# SheetBYB2A.net
KiCad netlist of a schematic drawn in Altium Designer
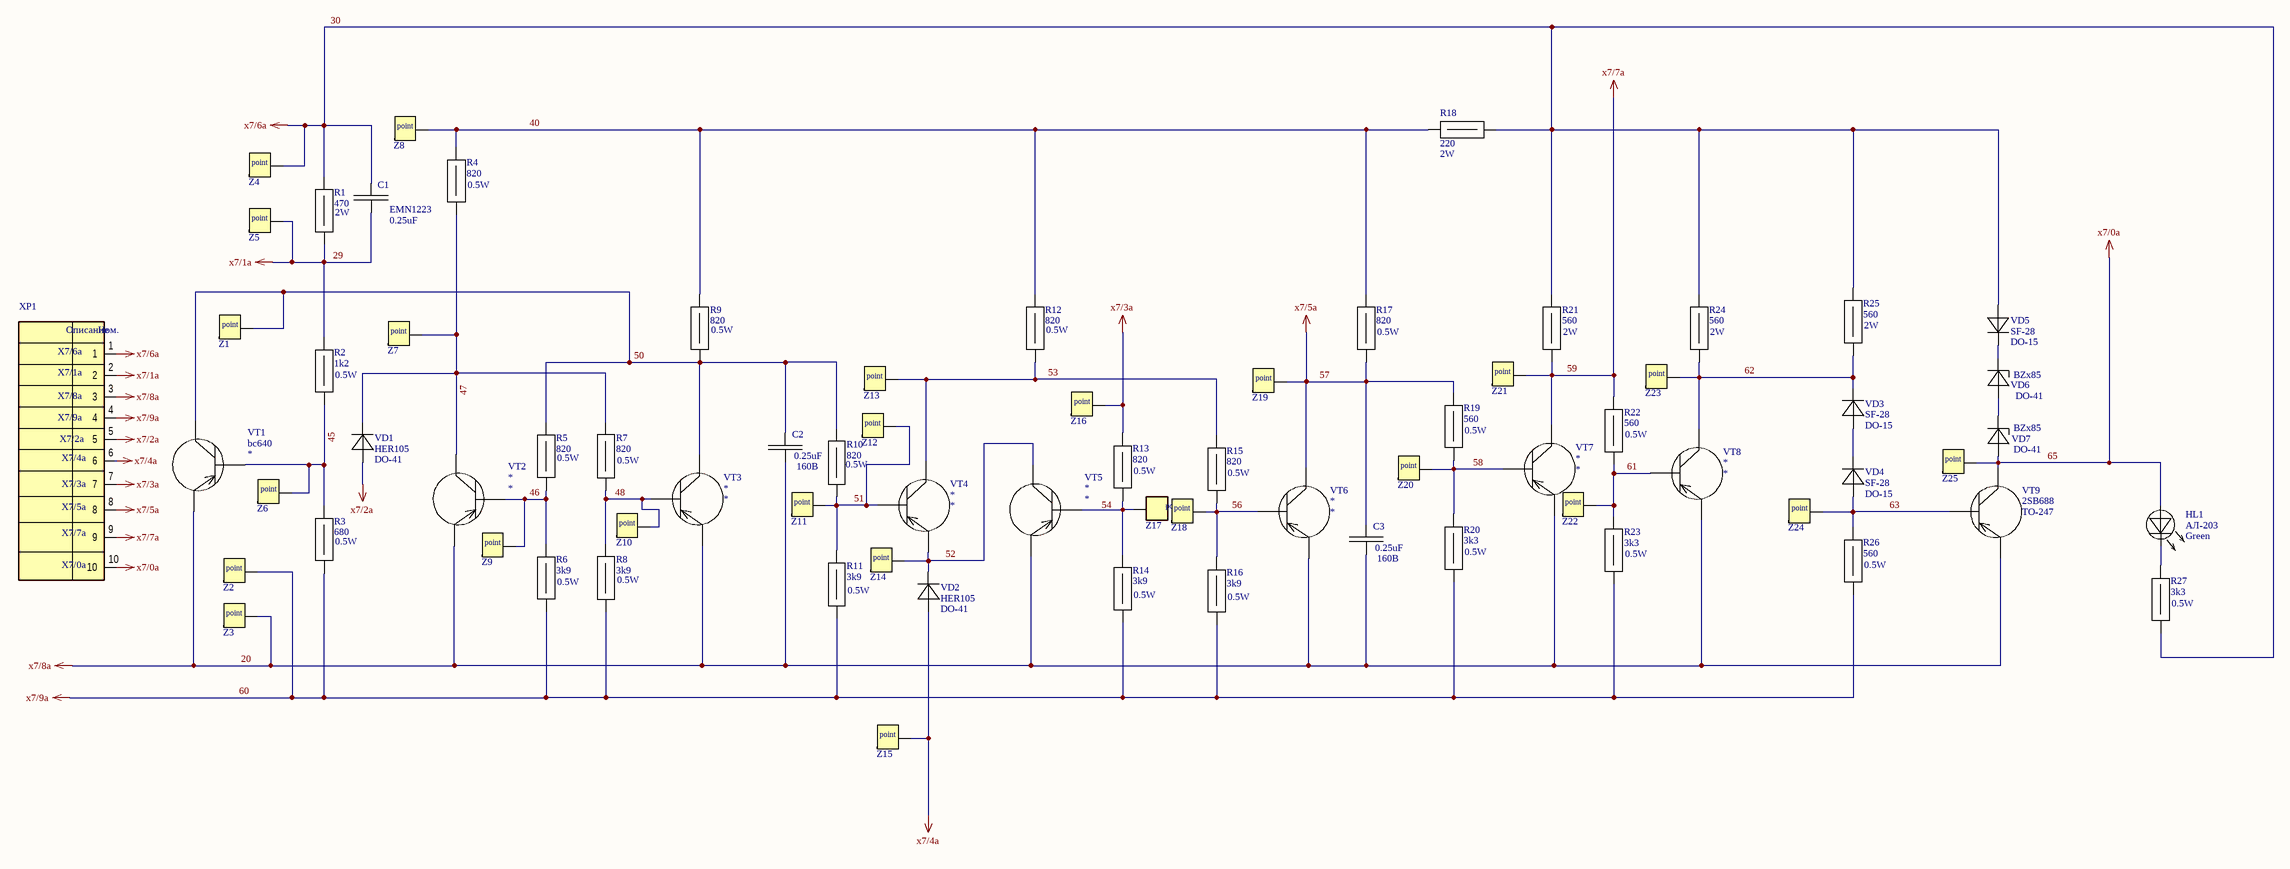
[diagram p0: SheetBYB2A.SchDoc]

(export (version "E")
  (design (tool "Eeschema 10.0.6"))
  (components
    (comp (ref "C1")
      (value "0.25uF")
      (footprint "Capasitor")
      (fields (field (name "MARKA") "EMN1223") (field (name "Comment") "Capasitor"))
      (libsource (lib "SchlibBYB2A") (part "Capasitor"))
    )
    (comp (ref "C2")
      (value "0.25uF")
      (footprint "Capasitor")
      (fields (field (name "VOLTAGE") "160B") (field (name "Comment") "Capasitor"))
      (libsource (lib "SchlibBYB2A") (part "Capasitor"))
    )
    (comp (ref "C3")
      (value "0.25uF")
      (footprint "Capasitor")
      (fields (field (name "VOLTAGE") "160B") (field (name "Comment") "Capasitor"))
      (libsource (lib "SchlibBYB2A") (part "Capasitor"))
    )
    (comp (ref "HL1")
      (value "Led")
      (footprint "GNLR")
      (fields (field (name "MARKA") "АЛ-203") (field (name "COLOR") "Green"))
      (libsource (lib "SchlibBYB2A") (part "Led"))
    )
    (comp (ref "R1")
      (value "470")
      (footprint "Resistor_2W")
      (fields (field (name "POWER") "2W") (field (name "Comment") "Resistor_1/2W"))
      (libsource (lib "SchlibBYB2A") (part "Resistor_1/2W"))
    )
    (comp (ref "R2")
      (value "1k2")
      (footprint "RESC5025L")
      (fields (field (name "POWER") "0.5W") (field (name "Comment") "Resistor_1/2W"))
      (libsource (lib "SchlibBYB2A") (part "Resistor_1/2W"))
    )
    (comp (ref "R3")
      (value "680")
      (footprint "RESC5025L")
      (fields (field (name "POWER") "0.5W") (field (name "Comment") "Resistor_1/2W"))
      (libsource (lib "SchlibBYB2A") (part "Resistor_1/2W"))
    )
    (comp (ref "R4")
      (value "820")
      (footprint "RESC5025L")
      (fields (field (name "POWER") "0.5W") (field (name "Comment") "Resistor_1/2W"))
      (libsource (lib "SchlibBYB2A") (part "Resistor_1/2W"))
    )
    (comp (ref "R5")
      (value "820")
      (footprint "RESC5025L")
      (fields (field (name "POWER") "0.5W") (field (name "Comment") "Resistor_1/2W"))
      (libsource (lib "SchlibBYB2A") (part "Resistor_1/2W"))
    )
    (comp (ref "R6")
      (value "3k9")
      (footprint "RESC5025L")
      (fields (field (name "POWER") "0.5W") (field (name "Comment") "Resistor_1/2W"))
      (libsource (lib "SchlibBYB2A") (part "Resistor_1/2W"))
    )
    (comp (ref "R7")
      (value "820")
      (footprint "RESC5025L")
      (fields (field (name "POWER") "0.5W") (field (name "Comment") "Resistor_1/2W"))
      (libsource (lib "SchlibBYB2A") (part "Resistor_1/2W"))
    )
    (comp (ref "R8")
      (value "3k9")
      (footprint "RESC5025L")
      (fields (field (name "POWER") "0.5W") (field (name "Comment") "Resistor_1/2W"))
      (libsource (lib "SchlibBYB2A") (part "Resistor_1/2W"))
    )
    (comp (ref "R9")
      (value "820")
      (footprint "RESC5025L")
      (fields (field (name "POWER") "0.5W") (field (name "Comment") "Resistor_1/2W"))
      (libsource (lib "SchlibBYB2A") (part "Resistor_1/2W"))
    )
    (comp (ref "R10")
      (value "820")
      (footprint "RESC5025L")
      (fields (field (name "POWER") "0.5W") (field (name "Comment") "Resistor_1/2W"))
      (libsource (lib "SchlibBYB2A") (part "Resistor_1/2W"))
    )
    (comp (ref "R11")
      (value "3k9")
      (footprint "RESC5025L")
      (fields (field (name "POWER") "0.5W") (field (name "Comment") "Resistor_1/2W"))
      (libsource (lib "SchlibBYB2A") (part "Resistor_1/2W"))
    )
    (comp (ref "R12")
      (value "820")
      (footprint "RESC5025L")
      (fields (field (name "POWER") "0.5W") (field (name "Comment") "Resistor_1/2W"))
      (libsource (lib "SchlibBYB2A") (part "Resistor_1/2W"))
    )
    (comp (ref "R13")
      (value "820")
      (footprint "RESC5025L")
      (fields (field (name "POWER") "0.5W") (field (name "Comment") "Resistor_1/2W"))
      (libsource (lib "SchlibBYB2A") (part "Resistor_1/2W"))
    )
    (comp (ref "R14")
      (value "3k9")
      (footprint "RESC5025L")
      (fields (field (name "POWER") "0.5W") (field (name "Comment") "Resistor_1/2W"))
      (libsource (lib "SchlibBYB2A") (part "Resistor_1/2W"))
    )
    (comp (ref "R15")
      (value "820")
      (footprint "RESC5025L")
      (fields (field (name "POWER") "0.5W") (field (name "Comment") "Resistor_1/2W"))
      (libsource (lib "SchlibBYB2A") (part "Resistor_1/2W"))
    )
    (comp (ref "R16")
      (value "3k9")
      (footprint "RESC5025L")
      (fields (field (name "POWER") "0.5W") (field (name "Comment") "Resistor_1/2W"))
      (libsource (lib "SchlibBYB2A") (part "Resistor_1/2W"))
    )
    (comp (ref "R17")
      (value "820")
      (footprint "RESC5025L")
      (fields (field (name "POWER") "0.5W") (field (name "Comment") "Resistor_1/2W"))
      (libsource (lib "SchlibBYB2A") (part "Resistor_1/2W"))
    )
    (comp (ref "R18")
      (value "220")
      (footprint "Resistor_2W")
      (fields (field (name "POWER") "2W") (field (name "Comment") "Resistor_1/2W"))
      (libsource (lib "SchlibBYB2A") (part "Resistor_1/2W"))
    )
    (comp (ref "R19")
      (value "560")
      (footprint "RESC5025L")
      (fields (field (name "POWER") "0.5W") (field (name "Comment") "Resistor_1/2W"))
      (libsource (lib "SchlibBYB2A") (part "Resistor_1/2W"))
    )
    (comp (ref "R20")
      (value "3k3")
      (footprint "RESC5025L")
      (fields (field (name "POWER") "0.5W") (field (name "Comment") "Resistor_1/2W"))
      (libsource (lib "SchlibBYB2A") (part "Resistor_1/2W"))
    )
    (comp (ref "R21")
      (value "560")
      (footprint "Resistor_2W")
      (fields (field (name "POWER") "2W") (field (name "Comment") "Resistor_1/2W"))
      (libsource (lib "SchlibBYB2A") (part "Resistor_1/2W"))
    )
    (comp (ref "R22")
      (value "560")
      (footprint "RESC5025L")
      (fields (field (name "POWER") "0.5W") (field (name "Comment") "Resistor_1/2W"))
      (libsource (lib "SchlibBYB2A") (part "Resistor_1/2W"))
    )
    (comp (ref "R23")
      (value "3k3")
      (footprint "RESC5025L")
      (fields (field (name "POWER") "0.5W") (field (name "Comment") "Resistor_1/2W"))
      (libsource (lib "SchlibBYB2A") (part "Resistor_1/2W"))
    )
    (comp (ref "R24")
      (value "560")
      (footprint "Resistor_2W")
      (fields (field (name "POWER") "2W") (field (name "Comment") "Resistor_1/2W"))
      (libsource (lib "SchlibBYB2A") (part "Resistor_1/2W"))
    )
    (comp (ref "R25")
      (value "560")
      (footprint "Resistor_2W")
      (fields (field (name "POWER") "2W") (field (name "Comment") "Resistor_1/2W"))
      (libsource (lib "SchlibBYB2A") (part "Resistor_1/2W"))
    )
    (comp (ref "R26")
      (value "560")
      (footprint "RESC5025L")
      (fields (field (name "POWER") "0.5W") (field (name "Comment") "Resistor_1/2W"))
      (libsource (lib "SchlibBYB2A") (part "Resistor_1/2W"))
    )
    (comp (ref "R27")
      (value "3k3")
      (footprint "RESC5025L")
      (fields (field (name "POWER") "0.5W") (field (name "Comment") "Resistor_1/2W"))
      (libsource (lib "SchlibBYB2A") (part "Resistor_1/2W"))
    )
    (comp (ref "VD1")
      (value "Diode")
      (footprint "DO-41-vertical")
      (fields (field (name "MARKA") "HER105") (field (name "PACKAGE") "DO-41"))
      (libsource (lib "SchlibBYB2A") (part "Diode"))
    )
    (comp (ref "VD2")
      (value "Diode")
      (footprint "DO-41-vertical")
      (fields (field (name "MARKA") "HER105") (field (name "PACKAGE") "DO-41"))
      (libsource (lib "SchlibBYB2A") (part "Diode"))
    )
    (comp (ref "VD3")
      (value "Diode")
      (footprint "DO-15-Vertical")
      (fields (field (name "MARKA") "SF-28") (field (name "PACKAGE") "DO-15"))
      (libsource (lib "SchlibBYB2A") (part "Diode"))
    )
    (comp (ref "VD4")
      (value "Diode")
      (footprint "DO-15-Vertical")
      (fields (field (name "MARKA") "SF-28") (field (name "PACKAGE") "DO-15"))
      (libsource (lib "SchlibBYB2A") (part "Diode"))
    )
    (comp (ref "VD5")
      (value "Diode")
      (footprint "DO-15-Vertical")
      (fields (field (name "MARKA") "SF-28") (field (name "PACKAGE") "DO-15"))
      (libsource (lib "SchlibBYB2A") (part "Diode"))
    )
    (comp (ref "VD6")
      (value "stabilizater")
      (footprint "DO-41-vertical")
      (fields (field (name "MARKA") "BZx85") (field (name "PACKAGE") "DO-41"))
      (libsource (lib "SchlibBYB2A") (part "stabilizater"))
    )
    (comp (ref "VD7")
      (value "stabilizater")
      (footprint "DO-41-vertical")
      (fields (field (name "MARKA") "BZx85") (field (name "PACKAGE") "DO-41"))
      (libsource (lib "SchlibBYB2A") (part "stabilizater"))
    )
    (comp (ref "VT1")
      (value "Bipolar Transistor")
      (footprint "TO-92")
      (fields (field (name "MARKA") "bc640") (field (name "PACKAGE") "*"))
      (libsource (lib "") (part "Bipolar Transistor_1"))
    )
    (comp (ref "VT2")
      (value "Bipolar Transistor")
      (footprint "TO-92")
      (fields (field (name "MARKA") "*") (field (name "PACKAGE") "*"))
      (libsource (lib "") (part "Bipolar Transistor_1"))
    )
    (comp (ref "VT3")
      (value "Bipolar Transistor")
      (footprint "TO-92")
      (fields (field (name "MARKA") "*") (field (name "PACKAGE") "*"))
      (libsource (lib "SchlibBYB2A") (part "Bipolar Transistor"))
    )
    (comp (ref "VT4")
      (value "Bipolar Transistor")
      (footprint "TO-92")
      (fields (field (name "MARKA") "*") (field (name "PACKAGE") "*"))
      (libsource (lib "SchlibBYB2A") (part "Bipolar Transistor"))
    )
    (comp (ref "VT5")
      (value "Bipolar Transistor")
      (footprint "TO-92")
      (fields (field (name "MARKA") "*") (field (name "PACKAGE") "*"))
      (libsource (lib "") (part "Bipolar Transistor_1"))
    )
    (comp (ref "VT6")
      (value "Bipolar Transistor")
      (footprint "TO-92")
      (fields (field (name "MARKA") "*") (field (name "PACKAGE") "*"))
      (libsource (lib "SchlibBYB2A") (part "Bipolar Transistor"))
    )
    (comp (ref "VT7")
      (value "Bipolar Transistor")
      (footprint "TO-92")
      (fields (field (name "MARKA") "*") (field (name "PACKAGE") "*"))
      (libsource (lib "SchlibBYB2A") (part "Bipolar Transistor"))
    )
    (comp (ref "VT8")
      (value "Bipolar Transistor")
      (footprint "TO-92")
      (fields (field (name "MARKA") "*") (field (name "PACKAGE") "*"))
      (libsource (lib "SchlibBYB2A") (part "Bipolar Transistor"))
    )
    (comp (ref "VT9")
      (value "2sb688")
      (footprint "TO-247-3")
      (fields (field (name "MARKA") "2SB688") (field (name "PACKAGE") "TO-247"))
      (libsource (lib "SchlibBYB2A") (part "2sb688"))
    )
    (comp (ref "XP1")
      (value "Connector")
      (footprint "Connector")
      (libsource (lib "SchlibBYB2A") (part "Connector"))
    )
    (comp (ref "Z1")
      (value "point_control")
      (footprint "point_control")
      (libsource (lib "SchlibBYB2A") (part "point_control"))
    )
    (comp (ref "Z2")
      (value "point_control")
      (footprint "point_control")
      (libsource (lib "SchlibBYB2A") (part "point_control"))
    )
    (comp (ref "Z3")
      (value "point_control")
      (footprint "point_control")
      (libsource (lib "SchlibBYB2A") (part "point_control"))
    )
    (comp (ref "Z4")
      (value "point_control")
      (footprint "point_control")
      (libsource (lib "SchlibBYB2A") (part "point_control"))
    )
    (comp (ref "Z5")
      (value "point_control")
      (footprint "point_control")
      (libsource (lib "SchlibBYB2A") (part "point_control"))
    )
    (comp (ref "Z6")
      (value "point_control")
      (footprint "point_control")
      (libsource (lib "SchlibBYB2A") (part "point_control"))
    )
    (comp (ref "Z7")
      (value "point_control")
      (footprint "point_control")
      (libsource (lib "SchlibBYB2A") (part "point_control"))
    )
    (comp (ref "Z8")
      (value "point_control")
      (footprint "point_control")
      (libsource (lib "SchlibBYB2A") (part "point_control"))
    )
    (comp (ref "Z9")
      (value "point_control")
      (footprint "point_control")
      (libsource (lib "SchlibBYB2A") (part "point_control"))
    )
    (comp (ref "Z10")
      (value "point_control")
      (footprint "point_control")
      (libsource (lib "SchlibBYB2A") (part "point_control"))
    )
    (comp (ref "Z11")
      (value "point_control")
      (footprint "point_control")
      (libsource (lib "SchlibBYB2A") (part "point_control"))
    )
    (comp (ref "Z12")
      (value "point_control")
      (footprint "point_control")
      (libsource (lib "SchlibBYB2A") (part "point_control"))
    )
    (comp (ref "Z13")
      (value "point_control")
      (footprint "point_control")
      (libsource (lib "SchlibBYB2A") (part "point_control"))
    )
    (comp (ref "Z14")
      (value "point_control")
      (footprint "point_control")
      (libsource (lib "SchlibBYB2A") (part "point_control"))
    )
    (comp (ref "Z15")
      (value "point_control")
      (footprint "point_control")
      (libsource (lib "SchlibBYB2A") (part "point_control"))
    )
    (comp (ref "Z16")
      (value "point_control")
      (footprint "point_control")
      (libsource (lib "SchlibBYB2A") (part "point_control"))
    )
    (comp (ref "Z17")
      (value "point_control")
      (footprint "point_control")
      (libsource (lib "") (part "point_control_1"))
    )
    (comp (ref "Z18")
      (value "point_control")
      (footprint "point_control")
      (libsource (lib "SchlibBYB2A") (part "point_control"))
    )
    (comp (ref "Z19")
      (value "point_control")
      (footprint "point_control")
      (libsource (lib "SchlibBYB2A") (part "point_control"))
    )
    (comp (ref "Z20")
      (value "point_control")
      (footprint "point_control")
      (libsource (lib "SchlibBYB2A") (part "point_control"))
    )
    (comp (ref "Z21")
      (value "point_control")
      (footprint "point_control")
      (libsource (lib "SchlibBYB2A") (part "point_control"))
    )
    (comp (ref "Z22")
      (value "point_control")
      (footprint "point_control")
      (libsource (lib "SchlibBYB2A") (part "point_control"))
    )
    (comp (ref "Z23")
      (value "point_control")
      (footprint "point_control")
      (libsource (lib "SchlibBYB2A") (part "point_control"))
    )
    (comp (ref "Z24")
      (value "point_control")
      (footprint "point_control")
      (libsource (lib "SchlibBYB2A") (part "point_control"))
    )
    (comp (ref "Z25")
      (value "point_control")
      (footprint "point_control")
      (libsource (lib "SchlibBYB2A") (part "point_control"))
    )
  )
  (nets
    (net (code "2") (name "/40") (class "Default")
      (node (ref "R12") (pin "2") (pinfunction "2_2") (pintype "passive"))
      (node (ref "R17") (pin "2") (pinfunction "2_2") (pintype "passive"))
      (node (ref "R18") (pin "2") (pinfunction "2_2") (pintype "passive"))
      (node (ref "R4") (pin "2") (pinfunction "2_2") (pintype "passive"))
      (node (ref "R9") (pin "2") (pinfunction "2_2") (pintype "passive"))
      (node (ref "Z8") (pin "1") (pinfunction "1_1") (pintype "passive"))
    )
    (net (code "3") (name "/45") (class "Default")
      (node (ref "R2") (pin "1") (pinfunction "1_1") (pintype "passive"))
      (node (ref "R3") (pin "2") (pinfunction "2_2") (pintype "passive"))
      (node (ref "VT1") (pin "3") (pinfunction "3_3") (pintype "passive"))
      (node (ref "Z6") (pin "1") (pinfunction "1_1") (pintype "passive"))
    )
    (net (code "4") (name "/46") (class "Default")
      (node (ref "R5") (pin "1") (pinfunction "1_1") (pintype "passive"))
      (node (ref "R6") (pin "2") (pinfunction "2_2") (pintype "passive"))
      (node (ref "VT2") (pin "3") (pinfunction "3_3") (pintype "passive"))
      (node (ref "Z9") (pin "1") (pinfunction "1_1") (pintype "passive"))
    )
    (net (code "5") (name "/47") (class "Default")
      (node (ref "R4") (pin "1") (pinfunction "1_1") (pintype "passive"))
      (node (ref "R7") (pin "2") (pinfunction "2_2") (pintype "passive"))
      (node (ref "VD1") (pin "2") (pinfunction "2_2") (pintype "passive"))
      (node (ref "VT2") (pin "2") (pinfunction "2_2") (pintype "passive"))
      (node (ref "Z7") (pin "1") (pinfunction "1_1") (pintype "passive"))
    )
    (net (code "6") (name "/48") (class "Default")
      (node (ref "R7") (pin "1") (pinfunction "1_1") (pintype "passive"))
      (node (ref "R8") (pin "2") (pinfunction "2_2") (pintype "passive"))
      (node (ref "VT3") (pin "3") (pinfunction "3_3") (pintype "passive"))
      (node (ref "Z10") (pin "1") (pinfunction "1_1") (pintype "passive"))
    )
    (net (code "7") (name "/50") (class "Default")
      (node (ref "C2") (pin "1") (pinfunction "1_1") (pintype "passive"))
      (node (ref "R10") (pin "2") (pinfunction "2_2") (pintype "passive"))
      (node (ref "R5") (pin "2") (pinfunction "2_2") (pintype "passive"))
      (node (ref "R9") (pin "1") (pinfunction "1_1") (pintype "passive"))
      (node (ref "VT1") (pin "2") (pinfunction "2_2") (pintype "passive"))
      (node (ref "VT3") (pin "2") (pinfunction "2_2") (pintype "passive"))
      (node (ref "Z1") (pin "1") (pinfunction "1_1") (pintype "passive"))
    )
    (net (code "8") (name "/51") (class "Default")
      (node (ref "R10") (pin "1") (pinfunction "1_1") (pintype "passive"))
      (node (ref "R11") (pin "2") (pinfunction "2_2") (pintype "passive"))
      (node (ref "VT4") (pin "3") (pinfunction "3_3") (pintype "passive"))
      (node (ref "Z11") (pin "1") (pinfunction "1_1") (pintype "passive"))
      (node (ref "Z12") (pin "1") (pinfunction "1_1") (pintype "passive"))
    )
    (net (code "9") (name "/52") (class "Default")
      (node (ref "VD2") (pin "2") (pinfunction "2_2") (pintype "passive"))
      (node (ref "VT4") (pin "1") (pinfunction "1_1") (pintype "passive"))
      (node (ref "VT5") (pin "2") (pinfunction "2_2") (pintype "passive"))
      (node (ref "Z14") (pin "1") (pinfunction "1_1") (pintype "passive"))
    )
    (net (code "10") (name "/53") (class "Default")
      (node (ref "R12") (pin "1") (pinfunction "1_1") (pintype "passive"))
      (node (ref "R15") (pin "2") (pinfunction "2_2") (pintype "passive"))
      (node (ref "VT4") (pin "2") (pinfunction "2_2") (pintype "passive"))
      (node (ref "Z13") (pin "1") (pinfunction "1_1") (pintype "passive"))
    )
    (net (code "12") (name "/56") (class "Default")
      (node (ref "R15") (pin "1") (pinfunction "1_1") (pintype "passive"))
      (node (ref "R16") (pin "2") (pinfunction "2_2") (pintype "passive"))
      (node (ref "VT6") (pin "3") (pinfunction "3_3") (pintype "passive"))
      (node (ref "Z18") (pin "1") (pinfunction "1_1") (pintype "passive"))
    )
    (net (code "13") (name "/58") (class "Default")
      (node (ref "R19") (pin "1") (pinfunction "1_1") (pintype "passive"))
      (node (ref "R20") (pin "2") (pinfunction "2_2") (pintype "passive"))
      (node (ref "VT7") (pin "3") (pinfunction "3_3") (pintype "passive"))
      (node (ref "Z20") (pin "1") (pinfunction "1_1") (pintype "passive"))
    )
    (net (code "14") (name "/61") (class "Default")
      (node (ref "R22") (pin "1") (pinfunction "1_1") (pintype "passive"))
      (node (ref "R23") (pin "2") (pinfunction "2_2") (pintype "passive"))
      (node (ref "VT8") (pin "3") (pinfunction "3_3") (pintype "passive"))
      (node (ref "Z22") (pin "1") (pinfunction "1_1") (pintype "passive"))
    )
    (net (code "15") (name "/62") (class "Default")
      (node (ref "R24") (pin "1") (pinfunction "1_1") (pintype "passive"))
      (node (ref "R25") (pin "1") (pinfunction "1_1") (pintype "passive"))
      (node (ref "VD3") (pin "2") (pinfunction "2_2") (pintype "passive"))
      (node (ref "VT8") (pin "2") (pinfunction "2_2") (pintype "passive"))
      (node (ref "Z23") (pin "1") (pinfunction "1_1") (pintype "passive"))
    )
    (net (code "16") (name "/63") (class "Default")
      (node (ref "R26") (pin "2") (pinfunction "2_2") (pintype "passive"))
      (node (ref "VD4") (pin "1") (pinfunction "1_1") (pintype "passive"))
      (node (ref "VT9") (pin "1") (pinfunction "1_1") (pintype "passive"))
      (node (ref "Z24") (pin "1") (pinfunction "1_1") (pintype "passive"))
    )
    (net (code "17") (name "Net-(HL1-Pad2)") (class "Default")
      (node (ref "HL1") (pin "2") (pinfunction "2_2") (pintype "passive"))
      (node (ref "R27") (pin "2") (pinfunction "2_2") (pintype "passive"))
    )
    (net (code "18") (name "Net-(R13-Pad1)") (class "Default")
      (node (ref "R13") (pin "1") (pinfunction "1_1") (pintype "passive"))
      (node (ref "R14") (pin "2") (pinfunction "2_2") (pintype "passive"))
      (node (ref "VT5") (pin "3") (pinfunction "3_3") (pintype "passive"))
      (node (ref "Z17") (pin "1") (pinfunction "1_1") (pintype "passive"))
    )
    (net (code "19") (name "Net-(VD3-Pad1)") (class "Default")
      (node (ref "VD3") (pin "1") (pinfunction "1_1") (pintype "passive"))
      (node (ref "VD4") (pin "2") (pinfunction "2_2") (pintype "passive"))
    )
    (net (code "20") (name "Net-(VD5-Pad2)") (class "Default")
      (node (ref "VD5") (pin "2") (pinfunction "2_2") (pintype "passive"))
      (node (ref "VD6") (pin "2") (pinfunction "2_2") (pintype "passive"))
    )
    (net (code "21") (name "Net-(VD6-Pad1)") (class "Default")
      (node (ref "VD6") (pin "1") (pinfunction "1_1") (pintype "passive"))
      (node (ref "VD7") (pin "2") (pinfunction "2_2") (pintype "passive"))
    )
    (net (code "22") (name "x7{slash}0a") (class "Default")
      (node (ref "HL1") (pin "1") (pinfunction "1_1") (pintype "passive"))
      (node (ref "VD7") (pin "1") (pinfunction "1_1") (pintype "passive"))
      (node (ref "VT9") (pin "2") (pinfunction "2_2") (pintype "passive"))
      (node (ref "XP1") (pin "10") (pinfunction "10_10") (pintype "passive"))
      (node (ref "Z25") (pin "1") (pinfunction "1_1") (pintype "passive"))
    )
    (net (code "23") (name "x7{slash}1a") (class "Default")
      (node (ref "C1") (pin "2") (pinfunction "2_2") (pintype "passive"))
      (node (ref "R1") (pin "1") (pinfunction "1_1") (pintype "passive"))
      (node (ref "R2") (pin "2") (pinfunction "2_2") (pintype "passive"))
      (node (ref "XP1") (pin "2") (pinfunction "2_2") (pintype "passive"))
      (node (ref "Z5") (pin "1") (pinfunction "1_1") (pintype "passive"))
    )
    (net (code "24") (name "x7{slash}2a") (class "Default")
      (node (ref "VD1") (pin "1") (pinfunction "1_1") (pintype "passive"))
      (node (ref "XP1") (pin "5") (pinfunction "5_5") (pintype "passive"))
    )
    (net (code "25") (name "x7{slash}3a") (class "Default")
      (node (ref "R13") (pin "2") (pinfunction "2_2") (pintype "passive"))
      (node (ref "XP1") (pin "7") (pinfunction "7_7") (pintype "passive"))
      (node (ref "Z16") (pin "1") (pinfunction "1_1") (pintype "passive"))
    )
    (net (code "26") (name "x7{slash}4a") (class "Default")
      (node (ref "VD2") (pin "1") (pinfunction "1_1") (pintype "passive"))
      (node (ref "XP1") (pin "6") (pinfunction "6_6") (pintype "passive"))
      (node (ref "Z15") (pin "1") (pinfunction "1_1") (pintype "passive"))
    )
    (net (code "27") (name "x7{slash}5a") (class "Default")
      (node (ref "C3") (pin "1") (pinfunction "1_1") (pintype "passive"))
      (node (ref "R17") (pin "1") (pinfunction "1_1") (pintype "passive"))
      (node (ref "R19") (pin "2") (pinfunction "2_2") (pintype "passive"))
      (node (ref "VT6") (pin "2") (pinfunction "2_2") (pintype "passive"))
      (node (ref "XP1") (pin "8") (pinfunction "8_8") (pintype "passive"))
      (node (ref "Z19") (pin "1") (pinfunction "1_1") (pintype "passive"))
    )
    (net (code "28") (name "x7{slash}6a") (class "Default")
      (node (ref "C1") (pin "1") (pinfunction "1_1") (pintype "passive"))
      (node (ref "R1") (pin "2") (pinfunction "2_2") (pintype "passive"))
      (node (ref "R18") (pin "1") (pinfunction "1_1") (pintype "passive"))
      (node (ref "R21") (pin "2") (pinfunction "2_2") (pintype "passive"))
      (node (ref "R24") (pin "2") (pinfunction "2_2") (pintype "passive"))
      (node (ref "R25") (pin "2") (pinfunction "2_2") (pintype "passive"))
      (node (ref "R27") (pin "1") (pinfunction "1_1") (pintype "passive"))
      (node (ref "VD5") (pin "1") (pinfunction "1_1") (pintype "passive"))
      (node (ref "XP1") (pin "1") (pinfunction "1_1") (pintype "passive"))
      (node (ref "Z4") (pin "1") (pinfunction "1_1") (pintype "passive"))
    )
    (net (code "29") (name "x7{slash}7a") (class "Default")
      (node (ref "R21") (pin "1") (pinfunction "1_1") (pintype "passive"))
      (node (ref "R22") (pin "2") (pinfunction "2_2") (pintype "passive"))
      (node (ref "VT7") (pin "2") (pinfunction "2_2") (pintype "passive"))
      (node (ref "XP1") (pin "9") (pinfunction "9_9") (pintype "passive"))
      (node (ref "Z21") (pin "1") (pinfunction "1_1") (pintype "passive"))
    )
    (net (code "30") (name "x7{slash}8a") (class "Default")
      (node (ref "C2") (pin "2") (pinfunction "2_2") (pintype "passive"))
      (node (ref "C3") (pin "2") (pinfunction "2_2") (pintype "passive"))
      (node (ref "VT1") (pin "1") (pinfunction "1_1") (pintype "passive"))
      (node (ref "VT2") (pin "1") (pinfunction "1_1") (pintype "passive"))
      (node (ref "VT3") (pin "1") (pinfunction "1_1") (pintype "passive"))
      (node (ref "VT5") (pin "1") (pinfunction "1_1") (pintype "passive"))
      (node (ref "VT6") (pin "1") (pinfunction "1_1") (pintype "passive"))
      (node (ref "VT7") (pin "1") (pinfunction "1_1") (pintype "passive"))
      (node (ref "VT8") (pin "1") (pinfunction "1_1") (pintype "passive"))
      (node (ref "VT9") (pin "3") (pinfunction "3_3") (pintype "passive"))
      (node (ref "XP1") (pin "3") (pinfunction "3_3") (pintype "passive"))
      (node (ref "Z3") (pin "1") (pinfunction "1_1") (pintype "passive"))
    )
    (net (code "31") (name "x7{slash}9a") (class "Default")
      (node (ref "R11") (pin "1") (pinfunction "1_1") (pintype "passive"))
      (node (ref "R14") (pin "1") (pinfunction "1_1") (pintype "passive"))
      (node (ref "R16") (pin "1") (pinfunction "1_1") (pintype "passive"))
      (node (ref "R20") (pin "1") (pinfunction "1_1") (pintype "passive"))
      (node (ref "R23") (pin "1") (pinfunction "1_1") (pintype "passive"))
      (node (ref "R26") (pin "1") (pinfunction "1_1") (pintype "passive"))
      (node (ref "R3") (pin "1") (pinfunction "1_1") (pintype "passive"))
      (node (ref "R6") (pin "1") (pinfunction "1_1") (pintype "passive"))
      (node (ref "R8") (pin "1") (pinfunction "1_1") (pintype "passive"))
      (node (ref "XP1") (pin "4") (pinfunction "4_4") (pintype "passive"))
      (node (ref "Z2") (pin "1") (pinfunction "1_1") (pintype "passive"))
    )
  )
)
